# LED_KEYBOARD.net
KiCad netlist of a schematic drawn in Altium Designer
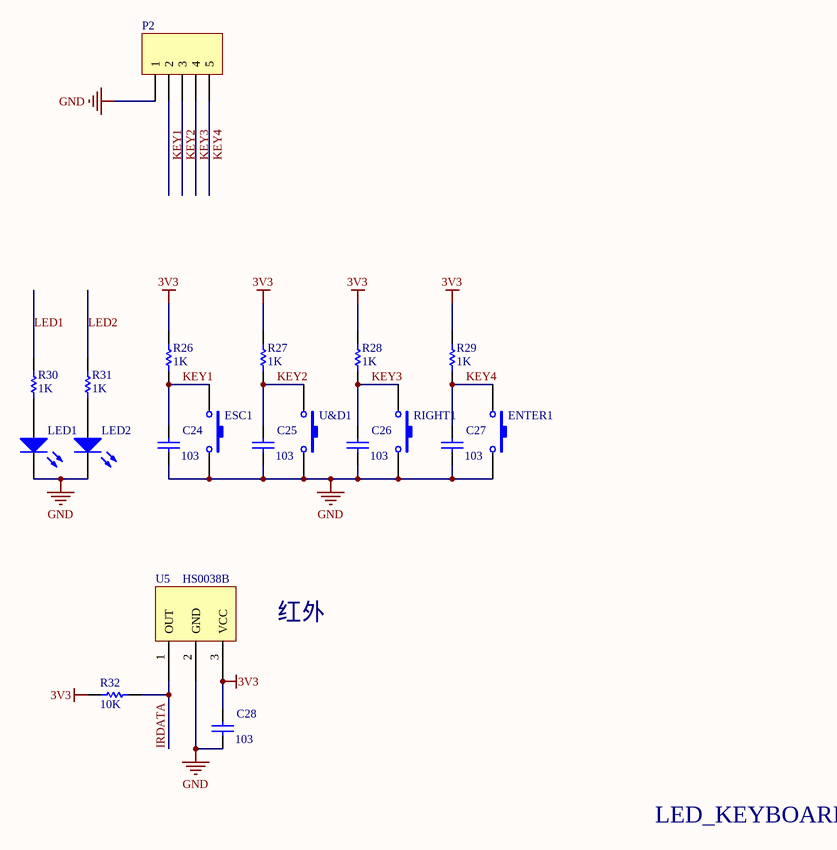
[diagram p0: LED_KEYBOARD.SchDoc]

(export (version "E")
  (design (tool "Eeschema 10.0.6"))
  (components
    (comp (ref "C24")
      (value "103")
      (footprint "RC0805")
      (description "Capacitor")
      (fields (field (name "Comment") "Cap") (field (name "PUBLISHER") "Altium Limited"))
      (libsource (lib "Miscellaneous Devices") (part "Cap"))
    )
    (comp (ref "C25")
      (value "103")
      (footprint "RC0805")
      (description "Capacitor")
      (fields (field (name "Comment") "Cap") (field (name "PUBLISHER") "Altium Limited"))
      (libsource (lib "Miscellaneous Devices") (part "Cap"))
    )
    (comp (ref "C26")
      (value "103")
      (footprint "RC0805")
      (description "Capacitor")
      (fields (field (name "Comment") "Cap") (field (name "PUBLISHER") "Altium Limited"))
      (libsource (lib "Miscellaneous Devices") (part "Cap"))
    )
    (comp (ref "C27")
      (value "103")
      (footprint "RC0805")
      (description "Capacitor")
      (fields (field (name "Comment") "Cap") (field (name "PUBLISHER") "Altium Limited"))
      (libsource (lib "Miscellaneous Devices") (part "Cap"))
    )
    (comp (ref "C28")
      (value "103")
      (footprint "RC0805")
      (description "Capacitor")
      (fields (field (name "Comment") "Cap") (field (name "PUBLISHER") "Altium Limited"))
      (libsource (lib "Miscellaneous Devices") (part "Cap"))
    )
    (comp (ref "ENTER1")
      (value "SW-PB")
      (footprint "BBTFT43_1704:小按键")
      (description "Switch")
      (fields (field (name "PUBLISHER") "Altium Limited"))
      (libsource (lib "Miscellaneous Devices") (part "SW-PB"))
    )
    (comp (ref "ESC1")
      (value "SW-PB")
      (footprint "BBTFT43_1704:小按键")
      (description "Switch")
      (fields (field (name "PUBLISHER") "Altium Limited"))
      (libsource (lib "Miscellaneous Devices") (part "SW-PB"))
    )
    (comp (ref "LED1")
      (value "LED0")
      (footprint "LED-0805")
      (description "Typical INFRARED GaAs LED")
      (fields (field (name "PUBLISHER") "Altium Limited"))
      (libsource (lib "Miscellaneous Devices") (part "LED0"))
    )
    (comp (ref "LED2")
      (value "LED0")
      (footprint "LED-0805")
      (description "Typical INFRARED GaAs LED")
      (fields (field (name "PUBLISHER") "Altium Limited"))
      (libsource (lib "Miscellaneous Devices") (part "LED0"))
    )
    (comp (ref "P2")
      (value "Header 5")
      (footprint "HDR1X5")
      (description "Header, 5-Pin")
      (fields (field (name "PUBLISHER") "Altium Limited"))
      (libsource (lib "Miscellaneous Connectors") (part "Header 5"))
    )
    (comp (ref "R26")
      (value "1K")
      (footprint "RC0805")
      (description "Resistor")
      (fields (field (name "Comment") "Res1") (field (name "PUBLISHER") "Altium Limited"))
      (libsource (lib "Miscellaneous Devices") (part "Res1"))
    )
    (comp (ref "R27")
      (value "1K")
      (footprint "RC0805")
      (description "Resistor")
      (fields (field (name "Comment") "Res1") (field (name "PUBLISHER") "Altium Limited"))
      (libsource (lib "Miscellaneous Devices") (part "Res1"))
    )
    (comp (ref "R28")
      (value "1K")
      (footprint "RC0805")
      (description "Resistor")
      (fields (field (name "Comment") "Res1") (field (name "PUBLISHER") "Altium Limited"))
      (libsource (lib "Miscellaneous Devices") (part "Res1"))
    )
    (comp (ref "R29")
      (value "1K")
      (footprint "RC0805")
      (description "Resistor")
      (fields (field (name "Comment") "Res1") (field (name "PUBLISHER") "Altium Limited"))
      (libsource (lib "Miscellaneous Devices") (part "Res1"))
    )
    (comp (ref "R30")
      (value "1K")
      (footprint "RC0805")
      (description "Resistor")
      (fields (field (name "Comment") "Res1") (field (name "PUBLISHER") "Altium Limited"))
      (libsource (lib "Miscellaneous Devices") (part "Res1"))
    )
    (comp (ref "R31")
      (value "1K")
      (footprint "RC0805")
      (description "Resistor")
      (fields (field (name "Comment") "Res1") (field (name "PUBLISHER") "Altium Limited"))
      (libsource (lib "Miscellaneous Devices") (part "Res1"))
    )
    (comp (ref "R32")
      (value "10K")
      (footprint "RC0805")
      (description "Resistor")
      (fields (field (name "Comment") "Res1") (field (name "PUBLISHER") "Altium Limited"))
      (libsource (lib "Miscellaneous Devices") (part "Res1"))
    )
    (comp (ref "RIGHT1")
      (value "SW-PB")
      (footprint "BBTFT43_1704:小按键")
      (description "Switch")
      (fields (field (name "PUBLISHER") "Altium Limited"))
      (libsource (lib "Miscellaneous Devices") (part "SW-PB"))
    )
    (comp (ref "U&D1")
      (value "SW-PB")
      (footprint "BBTFT43_1704:小按键")
      (description "Switch")
      (fields (field (name "PUBLISHER") "Altium Limited"))
      (libsource (lib "Miscellaneous Devices") (part "SW-PB"))
    )
    (comp (ref "U5") (value "HS0038B") (footprint "HS0038") (libsource (lib "STM32F103VE") (part "HS0038B")))
  )
  (nets
    (net (code "1") (name "/IRDATA") (class "Default")
      (node (ref "R32") (pin "2") (pinfunction "2_2") (pintype "passive"))
      (node (ref "U5") (pin "1") (pinfunction "OUT_1") (pintype "passive"))
    )
    (net (code "2") (name "/KEY1") (class "Default")
      (node (ref "C24") (pin "2") (pinfunction "2_2") (pintype "passive"))
      (node (ref "ESC1") (pin "1") (pinfunction "1_1") (pintype "passive"))
      (node (ref "P2") (pin "2") (pinfunction "2_2") (pintype "passive"))
      (node (ref "R26") (pin "2") (pinfunction "2_2") (pintype "passive"))
    )
    (net (code "3") (name "/KEY2") (class "Default")
      (node (ref "C25") (pin "2") (pinfunction "2_2") (pintype "passive"))
      (node (ref "P2") (pin "3") (pinfunction "3_3") (pintype "passive"))
      (node (ref "R27") (pin "2") (pinfunction "2_2") (pintype "passive"))
      (node (ref "U&D1") (pin "1") (pinfunction "1_1") (pintype "passive"))
    )
    (net (code "4") (name "/KEY3") (class "Default")
      (node (ref "C26") (pin "2") (pinfunction "2_2") (pintype "passive"))
      (node (ref "P2") (pin "4") (pinfunction "4_4") (pintype "passive"))
      (node (ref "R28") (pin "2") (pinfunction "2_2") (pintype "passive"))
      (node (ref "RIGHT1") (pin "1") (pinfunction "1_1") (pintype "passive"))
    )
    (net (code "5") (name "/KEY4") (class "Default")
      (node (ref "C27") (pin "2") (pinfunction "2_2") (pintype "passive"))
      (node (ref "ENTER1") (pin "1") (pinfunction "1_1") (pintype "passive"))
      (node (ref "P2") (pin "5") (pinfunction "5_5") (pintype "passive"))
      (node (ref "R29") (pin "2") (pinfunction "2_2") (pintype "passive"))
    )
    (net (code "6") (name "/LED1") (class "Default")
      (node (ref "R30") (pin "2") (pinfunction "2_2") (pintype "passive"))
    )
    (net (code "7") (name "/LED2") (class "Default")
      (node (ref "R31") (pin "2") (pinfunction "2_2") (pintype "passive"))
    )
    (net (code "8") (name "3V3") (class "Default")
      (node (ref "C28") (pin "2") (pinfunction "2_2") (pintype "passive"))
      (node (ref "R26") (pin "1") (pinfunction "1_1") (pintype "passive"))
      (node (ref "R27") (pin "1") (pinfunction "1_1") (pintype "passive"))
      (node (ref "R28") (pin "1") (pinfunction "1_1") (pintype "passive"))
      (node (ref "R29") (pin "1") (pinfunction "1_1") (pintype "passive"))
      (node (ref "R32") (pin "1") (pinfunction "1_1") (pintype "passive"))
      (node (ref "U5") (pin "3") (pinfunction "VCC_3") (pintype "passive"))
    )
    (net (code "9") (name "GND") (class "Default")
      (node (ref "C24") (pin "1") (pinfunction "1_1") (pintype "passive"))
      (node (ref "C25") (pin "1") (pinfunction "1_1") (pintype "passive"))
      (node (ref "C26") (pin "1") (pinfunction "1_1") (pintype "passive"))
      (node (ref "C27") (pin "1") (pinfunction "1_1") (pintype "passive"))
      (node (ref "C28") (pin "1") (pinfunction "1_1") (pintype "passive"))
      (node (ref "ENTER1") (pin "2") (pinfunction "2_2") (pintype "passive"))
      (node (ref "ESC1") (pin "2") (pinfunction "2_2") (pintype "passive"))
      (node (ref "LED1") (pin "2") (pinfunction "K_2") (pintype "passive"))
      (node (ref "LED2") (pin "2") (pinfunction "K_2") (pintype "passive"))
      (node (ref "P2") (pin "1") (pinfunction "1_1") (pintype "passive"))
      (node (ref "RIGHT1") (pin "2") (pinfunction "2_2") (pintype "passive"))
      (node (ref "U&D1") (pin "2") (pinfunction "2_2") (pintype "passive"))
      (node (ref "U5") (pin "2") (pinfunction "GND_2") (pintype "passive"))
    )
    (net (code "10") (name "Net-(LED1-A)") (class "Default")
      (node (ref "LED1") (pin "1") (pinfunction "A_1") (pintype "passive"))
      (node (ref "R30") (pin "1") (pinfunction "1_1") (pintype "passive"))
    )
    (net (code "11") (name "Net-(LED2-A)") (class "Default")
      (node (ref "LED2") (pin "1") (pinfunction "A_1") (pintype "passive"))
      (node (ref "R31") (pin "1") (pinfunction "1_1") (pintype "passive"))
    )
  )
)
